# Safety.net
KiCad netlist of a schematic drawn in Altium Designer
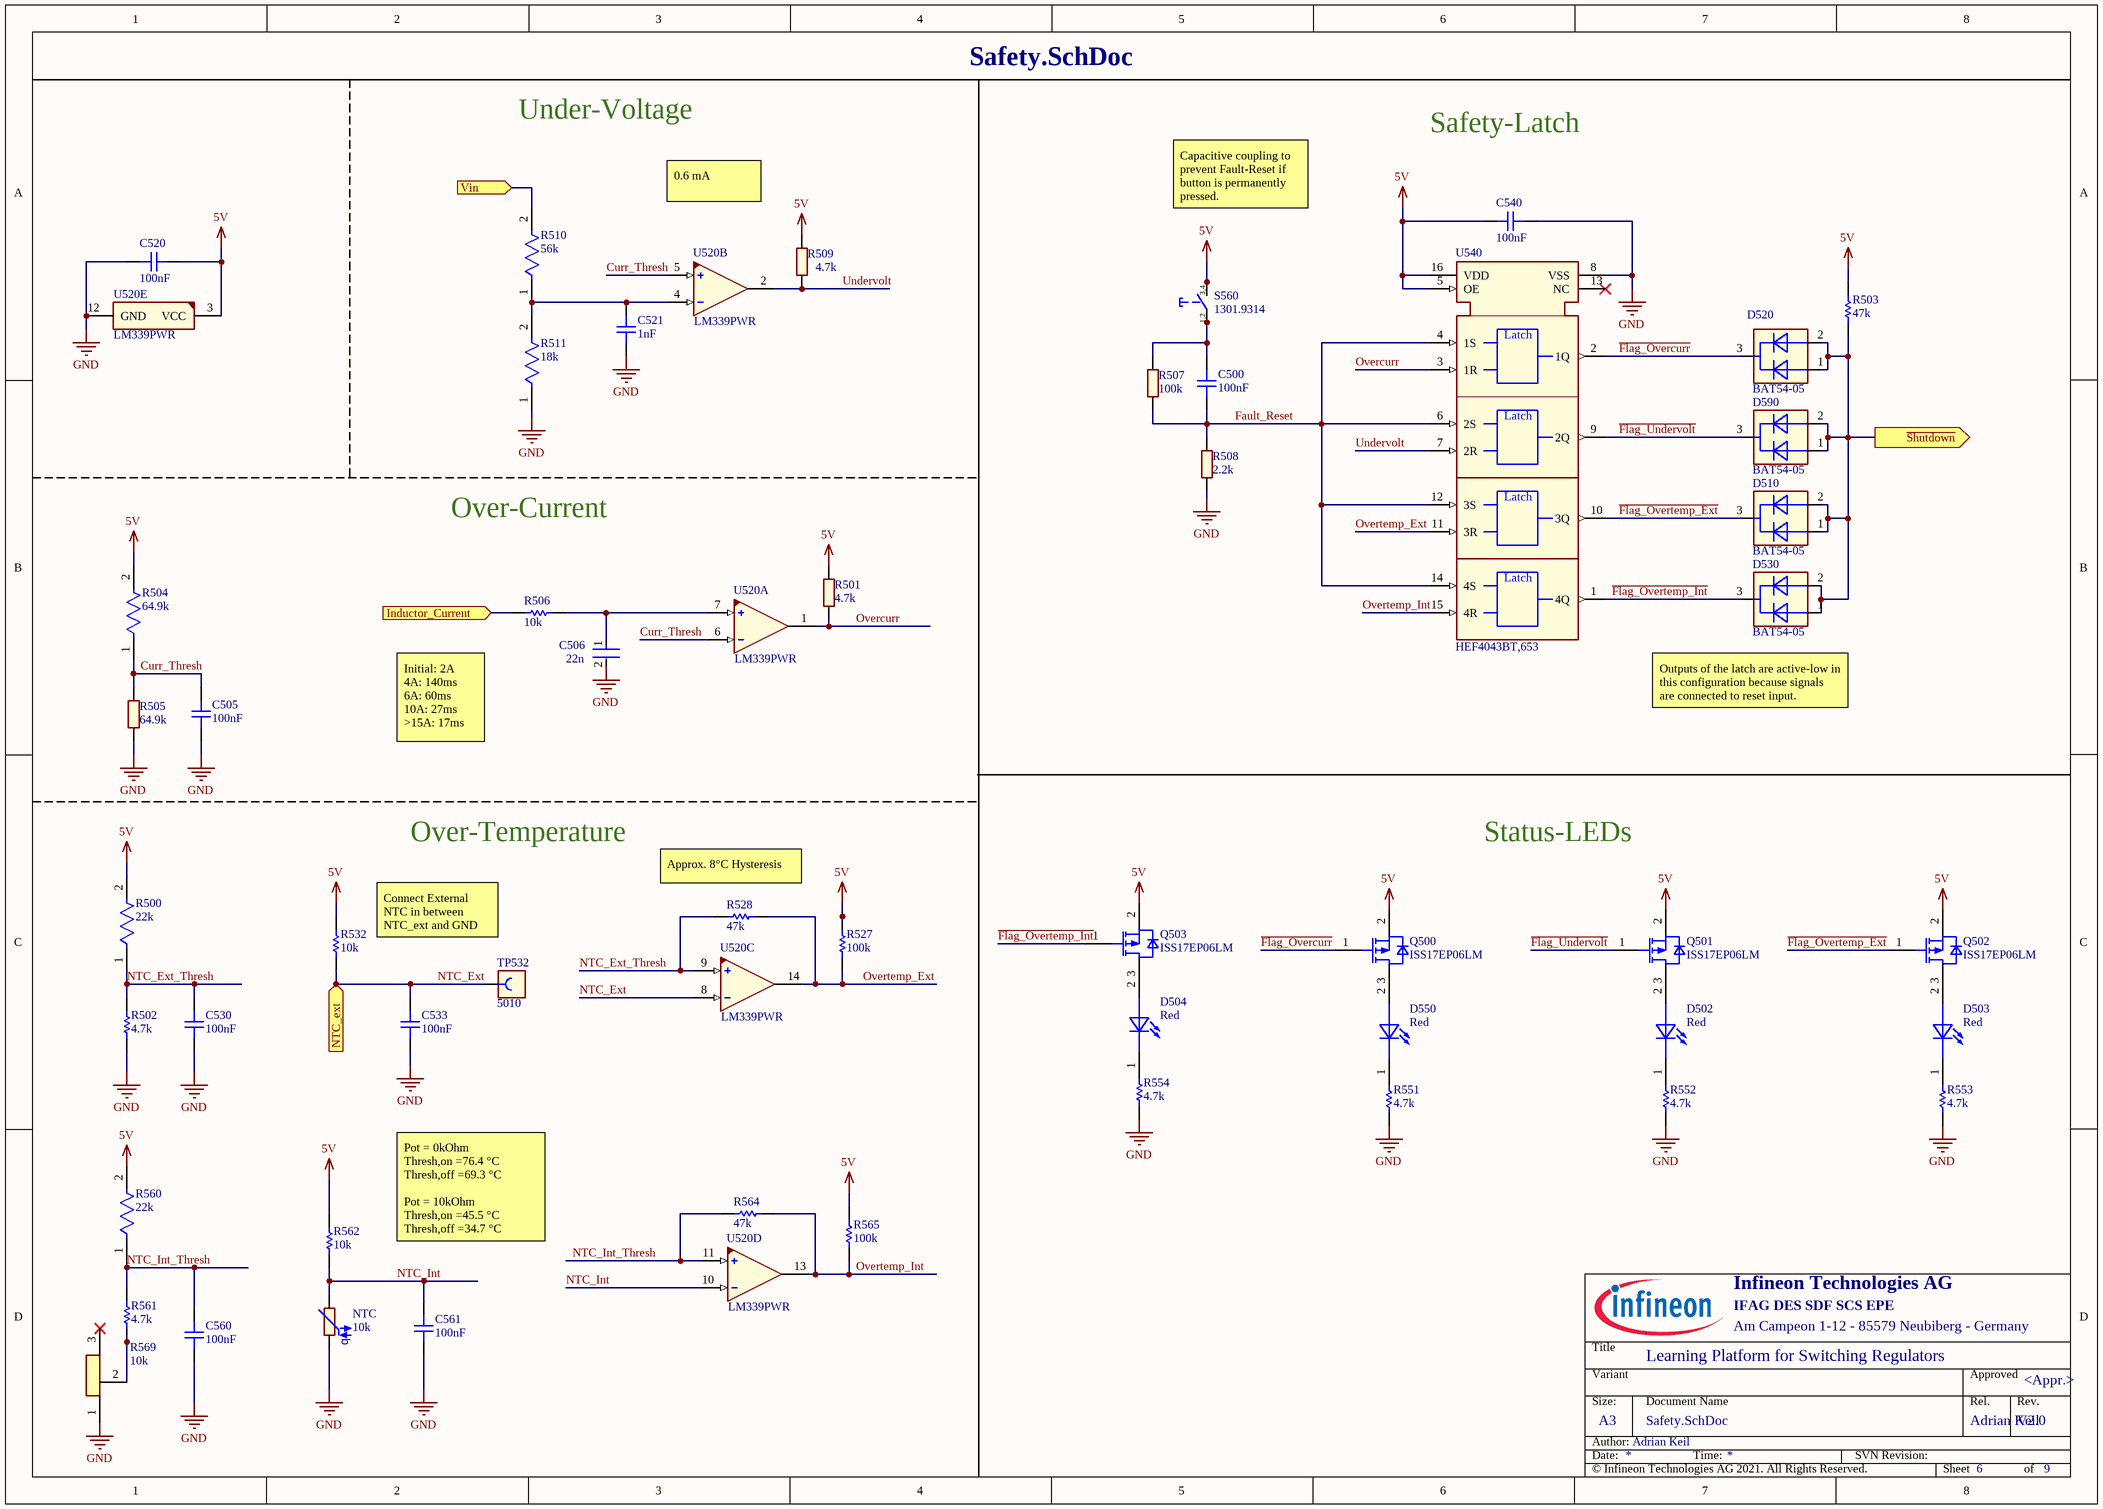
[diagram p0: Safety.SchDoc]

(export (version "E")
  (design (tool "Eeschema 10.0.6"))
  (components
    (comp (ref "C500")
      (value "100nF")
      (footprint "CAPC3216X125N-0")
      (description "CAP / CERA / 100nF / 50V / 10% / X7R (EIA) / -55°C to 125°C / 1206(3216) / SMD / -")
      (fields (field (name "LEGACY PARTNUMBER") "CAP01005660") (field (name "MANUFACTURER") "MuRata"))
      (libsource (lib "PCBLibraryData") (part "CAP-SGL-STD-02P_00000001"))
    )
    (comp (ref "C505")
      (value "100nF")
      (footprint "CAPC3216X125N-0")
      (description "CAP / CERA / 100nF / 50V / 10% / X7R (EIA) / -55°C to 125°C / 1206(3216) / SMD / -")
      (fields (field (name "LEGACY PARTNUMBER") "CAP01005660") (field (name "MANUFACTURER") "MuRata"))
      (libsource (lib "PCBLibraryData") (part "CAP-SGL-STD-02P_00000001"))
    )
    (comp (ref "C506")
      (value "22n")
      (footprint "FP-GRM319-0_15-IPC_C")
      (description "Chip Multilayer Ceramic Capacitors for General Purpose, 1206, 22000pF, C0G, 30ppm/°C, 5%, 50V")
      (fields (field (name "VOLTAGE") "50V") (field (name "TOLERANCE") "5%"))
      (libsource (lib "Altium Content Vault") (part "b4654b650e69147ec39a6b967a45e02"))
    )
    (comp (ref "C520")
      (value "100nF")
      (footprint "CAPC3216X125N-0")
      (description "CAP / CERA / 100nF / 50V / 10% / X7R (EIA) / -55°C to 125°C / 1206(3216) / SMD / -")
      (fields (field (name "LEGACY PARTNUMBER") "CAP01005660") (field (name "MANUFACTURER") "MuRata"))
      (libsource (lib "PCBLibraryData") (part "CAP-SGL-STD-02P_00000001"))
    )
    (comp (ref "C521")
      (value "1nF")
      (footprint "CAPC3216X95N")
      (description "CAP / CERA / 1nF / 50V / 10% / X7R (EIA) / -55°C to 125°C / 1206(3216) / SMD / -")
      (fields (field (name "LEGACY PARTNUMBER") "CAP01005183") (field (name "MANUFACTURER") "MuRata"))
      (libsource (lib "PCBLibraryData") (part "CAP-SGL-STD-02P_00000001"))
    )
    (comp (ref "C530")
      (value "100nF")
      (footprint "CAPC3216X125N-0")
      (description "CAP / CERA / 100nF / 50V / 10% / X7R (EIA) / -55°C to 125°C / 1206(3216) / SMD / -")
      (fields (field (name "LEGACY PARTNUMBER") "CAP01005660") (field (name "MANUFACTURER") "MuRata"))
      (libsource (lib "PCBLibraryData") (part "CAP-SGL-STD-02P_00000001"))
    )
    (comp (ref "C533")
      (value "100nF")
      (footprint "CAPC3216X125N-0")
      (description "CAP / CERA / 100nF / 50V / 10% / X7R (EIA) / -55°C to 125°C / 1206(3216) / SMD / -")
      (fields (field (name "LEGACY PARTNUMBER") "CAP01005660") (field (name "MANUFACTURER") "MuRata"))
      (libsource (lib "PCBLibraryData") (part "CAP-SGL-STD-02P_00000001"))
    )
    (comp (ref "C540")
      (value "100nF")
      (footprint "CAPC3216X125N-0")
      (description "CAP / CERA / 100nF / 50V / 10% / X7R (EIA) / -55°C to 125°C / 1206(3216) / SMD / -")
      (fields (field (name "LEGACY PARTNUMBER") "CAP01005660") (field (name "MANUFACTURER") "MuRata"))
      (libsource (lib "PCBLibraryData") (part "CAP-SGL-STD-02P_00000001"))
    )
    (comp (ref "C560")
      (value "100nF")
      (footprint "CAPC3216X125N-0")
      (description "CAP / CERA / 100nF / 50V / 10% / X7R (EIA) / -55°C to 125°C / 1206(3216) / SMD / -")
      (fields (field (name "LEGACY PARTNUMBER") "CAP01005660") (field (name "MANUFACTURER") "MuRata"))
      (libsource (lib "PCBLibraryData") (part "CAP-SGL-STD-02P_00000001"))
    )
    (comp (ref "C561")
      (value "100nF")
      (footprint "CAPC3216X125N-0")
      (description "CAP / CERA / 100nF / 50V / 10% / X7R (EIA) / -55°C to 125°C / 1206(3216) / SMD / -")
      (fields (field (name "LEGACY PARTNUMBER") "CAP01005660") (field (name "MANUFACTURER") "MuRata"))
      (libsource (lib "PCBLibraryData") (part "CAP-SGL-STD-02P_00000001"))
    )
    (comp (ref "D502")
      (value "Red")
      (footprint "LEDSC160X80X80-2N-1")
      (description "WL-SMCW SMT Mono-color Chip LED Waterclear, Red,630nm")
      (fields (field (name "MANUFACTURER") "Wurth Elektronik"))
      (libsource (lib "PCBLibraryData") (part "d_led_a"))
    )
    (comp (ref "D503")
      (value "Red")
      (footprint "LEDSC160X80X80-2N-1")
      (description "WL-SMCW SMT Mono-color Chip LED Waterclear, Red,630nm")
      (fields (field (name "MANUFACTURER") "Wurth Elektronik"))
      (libsource (lib "PCBLibraryData") (part "d_led_a"))
    )
    (comp (ref "D504")
      (value "Red")
      (footprint "LEDSC160X80X80-2N-1")
      (description "WL-SMCW SMT Mono-color Chip LED Waterclear, Red,630nm")
      (fields (field (name "MANUFACTURER") "Wurth Elektronik"))
      (libsource (lib "PCBLibraryData") (part "d_led_a"))
    )
    (comp (ref "D510")
      (value "BAT54-05")
      (footprint "SOT95P240X110-3N-1-V")
      (description "Silicon Schottky Diode, LS(nH) 1.8, VR 30V")
      (fields
        (field (name "LEGACY PARTNUMBER") "IFX01401370")
        (field (name "MANUFACTURER") "Infineon Technologies")
      )
      (libsource (lib "PCBLibraryData") (part "d_dual_a1a2c3_3p"))
    )
    (comp (ref "D520")
      (value "BAT54-05")
      (footprint "SOT95P240X110-3N-1-V")
      (description "Silicon Schottky Diode, LS(nH) 1.8, VR 30V")
      (fields
        (field (name "LEGACY PARTNUMBER") "IFX01401370")
        (field (name "MANUFACTURER") "Infineon Technologies")
      )
      (libsource (lib "PCBLibraryData") (part "d_dual_a1a2c3_3p"))
    )
    (comp (ref "D530")
      (value "BAT54-05")
      (footprint "SOT95P240X110-3N-1-V")
      (description "Silicon Schottky Diode, LS(nH) 1.8, VR 30V")
      (fields
        (field (name "LEGACY PARTNUMBER") "IFX01401370")
        (field (name "MANUFACTURER") "Infineon Technologies")
      )
      (libsource (lib "PCBLibraryData") (part "d_dual_a1a2c3_3p"))
    )
    (comp (ref "D550")
      (value "Red")
      (footprint "LEDSC160X80X80-2N-1")
      (description "WL-SMCW SMT Mono-color Chip LED Waterclear, Red,630nm")
      (fields (field (name "MANUFACTURER") "Wurth Elektronik"))
      (libsource (lib "PCBLibraryData") (part "d_led_a"))
    )
    (comp (ref "D590")
      (value "BAT54-05")
      (footprint "SOT95P240X110-3N-1-V")
      (description "Silicon Schottky Diode, LS(nH) 1.8, VR 30V")
      (fields
        (field (name "LEGACY PARTNUMBER") "IFX01401370")
        (field (name "MANUFACTURER") "Infineon Technologies")
      )
      (libsource (lib "PCBLibraryData") (part "d_dual_a1a2c3_3p"))
    )
    (comp (ref "NTC")
      (value "10k")
      (footprint "RESC1608X95N-1")
      (description "RES / NTC / 10k / 100mW / 1% / - / -40°C to 125°C / 0603(1608) / SMD / -")
      (fields (field (name "LEGACY PARTNUMBER") "RES01806219") (field (name "MANUFACTURER") "MuRata"))
      (libsource (lib "PCBLibraryData") (part "RES-SGL-NTC-02P_00000007"))
    )
    (comp (ref "Q500")
      (value "ISS17EP06LM")
      (footprint "SOT95P240X110-3N-1-V")
      (description "OptiMOSTM Small Signal Transistor, -60 V")
      (fields (field (name "MANUFACTURER") "Infineon Technologies"))
      (libsource (lib "PCBLibraryData") (part "igfet_p_ch_enh_dio_1g2s3d_3p"))
    )
    (comp (ref "Q501")
      (value "ISS17EP06LM")
      (footprint "SOT95P240X110-3N-1-V")
      (description "OptiMOSTM Small Signal Transistor, -60 V")
      (fields (field (name "MANUFACTURER") "Infineon Technologies"))
      (libsource (lib "PCBLibraryData") (part "igfet_p_ch_enh_dio_1g2s3d_3p"))
    )
    (comp (ref "Q502")
      (value "ISS17EP06LM")
      (footprint "SOT95P240X110-3N-1-V")
      (description "OptiMOSTM Small Signal Transistor, -60 V")
      (fields (field (name "MANUFACTURER") "Infineon Technologies"))
      (libsource (lib "PCBLibraryData") (part "igfet_p_ch_enh_dio_1g2s3d_3p"))
    )
    (comp (ref "Q503")
      (value "ISS17EP06LM")
      (footprint "SOT95P240X110-3N-1-V")
      (description "OptiMOSTM Small Signal Transistor, -60 V")
      (fields (field (name "MANUFACTURER") "Infineon Technologies"))
      (libsource (lib "PCBLibraryData") (part "igfet_p_ch_enh_dio_1g2s3d_3p"))
    )
    (comp (ref "R500")
      (value "22k")
      (footprint "FP-CRCW1206-e3-IPC_A")
      (description "RES Thick Film, 22kΩ, 1%, 0.25W, 100ppm/°C, 1206")
      (fields (field (name "TOLERANCE") "1%"))
      (libsource (lib "Altium Content Vault") (part "1029c3af85768c4190bb7ad29bc67b5"))
    )
    (comp (ref "R501")
      (value "4.7k")
      (footprint "RESC3216X60N")
      (description "RES / STD / 4.7k / 250mW / 1% / 100ppm/K / -55°C to 155°C / 1206(3216) / SMD / -")
      (fields (field (name "LEGACY PARTNUMBER") "RES01802819") (field (name "MANUFACTURER") "Vishay"))
      (libsource (lib "PCBLibraryData") (part "RES-SGL-STD-02P_00000006"))
    )
    (comp (ref "R502")
      (value "4.7k")
      (footprint "RESC3216X60X45ML15T20")
      (description "Chip Resistor, 4.7 KOhm, +/- 1%, 0.25 W, -55 to 155 degC, 1206 (3216 Metric), RoHS, Tape and Reel")
      (fields (field (name "MANUFACTURER") "Vishay Semiconductor") (field (name "TOLERANCE") "1%"))
      (libsource (lib "Altium Content Vault") (part "RES-2"))
    )
    (comp (ref "R503")
      (value "47k")
      (footprint "RESC3216X60X45LL10T20")
      (fields (field (name "PART NUMBER") "CRCW120647K0FKEA") (field (name "MANUFACTURER") "Vishay Dale"))
      (libsource (lib "Altium Content Vault") (part "RES"))
    )
    (comp (ref "R504")
      (value "64.9k")
      (footprint "FP-CRCW1206-e3-IPC_C")
      (description "RES Thick Film, 64.9kΩ, 1%, 0.25W, 100ppm/°C, 1206")
      (fields (field (name "TOLERANCE") "1%") (field (name "LCSC PART #") "C274045"))
      (libsource (lib "Altium Content Vault") (part "1029c3af85768c4190bb7ad29bc67b5"))
    )
    (comp (ref "R505")
      (value "64.9k")
      (footprint "RESC3216X60N")
      (description "RES / STD / 64.9k / 250mW / 1% / 100ppm/K / -55°C to 155°C / 1206(3216) / SMD / -")
      (fields (field (name "LEGACY PARTNUMBER") "RES01802950") (field (name "MANUFACTURER") "Vishay"))
      (libsource (lib "PCBLibraryData") (part "RES-SGL-STD-02P_00000006"))
    )
    (comp (ref "R506")
      (value "10k")
      (footprint "RESC3116X65X50NL20T20")
      (fields
        (field (name "PART NUMBER") "CRCW120610K0FKEAHP")
        (field (name "MANUFACTURER") "Vishay Dale")
        (field (name "LCSC PART #") "C313977")
      )
      (libsource (lib "Altium Content Vault") (part "RES"))
    )
    (comp (ref "R507")
      (value "100k")
      (footprint "RESC3216X60N")
      (description "RES / STD / 100k / 250mW / 1% / 100ppm/K / -55°C to 155°C / 1206(3216) / SMD / -")
      (fields (field (name "LEGACY PARTNUMBER") "RES01802971") (field (name "MANUFACTURER") "Vishay"))
      (libsource (lib "PCBLibraryData") (part "RES-SGL-STD-02P_00000006"))
    )
    (comp (ref "R508")
      (value "2.2k")
      (footprint "RESC3216X60N")
      (description "RES / STD / 2.2k / 250mW / 1% / 100ppm/K / -55°C to 155°C / 1206(3216) / SMD / -")
      (fields (field (name "LEGACY PARTNUMBER") "RES01802779") (field (name "MANUFACTURER") "Vishay"))
      (libsource (lib "") (part "RES-SGL-STD-02P_00000006_1"))
    )
    (comp (ref "R509")
      (value "4.7k")
      (footprint "RESC3216X60N")
      (description "RES / STD / 4.7k / 250mW / 1% / 100ppm/K / -55°C to 155°C / 1206(3216) / SMD / -")
      (fields (field (name "LEGACY PARTNUMBER") "RES01802819") (field (name "MANUFACTURER") "Vishay"))
      (libsource (lib "PCBLibraryData") (part "RES-SGL-STD-02P_00000006"))
    )
    (comp (ref "R510")
      (value "56k")
      (footprint "FP-CRCW1206-e3-IPC_C")
      (description "RES Thick Film, 56kΩ, 1%, 0.25W, 100ppm/°C, 1206")
      (fields (field (name "TOLERANCE") "1%") (field (name "LCSC PART #") "C137251"))
      (libsource (lib "Altium Content Vault") (part "1029c3af85768c4190bb7ad29bc67b5"))
    )
    (comp (ref "R511")
      (value "18k")
      (footprint "FP-CRCW1206-e3-IPC_C")
      (description "RES Thick Film, 18kΩ, 1%, 0.25W, 100ppm/°C, 1206")
      (fields (field (name "TOLERANCE") "1%"))
      (libsource (lib "Altium Content Vault") (part "1029c3af85768c4190bb7ad29bc67b5"))
    )
    (comp (ref "R527")
      (value "100k")
      (footprint "RESC3216X60X45NL10T20")
      (fields (field (name "PART NUMBER") "CRCW1206100KFKEA") (field (name "MANUFACTURER") "Vishay Dale"))
      (libsource (lib "Altium Content Vault") (part "RES"))
    )
    (comp (ref "R528")
      (value "47k")
      (footprint "RESC3216X60X45LL10T20")
      (fields (field (name "PART NUMBER") "CRCW120647K0FKEA") (field (name "MANUFACTURER") "Vishay Dale"))
      (libsource (lib "Altium Content Vault") (part "RES"))
    )
    (comp (ref "R532")
      (value "10k")
      (footprint "RESC3116X65X50NL20T20")
      (fields (field (name "PART NUMBER") "CRCW120610K0FKEAHP") (field (name "MANUFACTURER") "Vishay Dale"))
      (libsource (lib "Altium Content Vault") (part "RES"))
    )
    (comp (ref "R551")
      (value "4.7k")
      (footprint "RESC3216X60X45ML15T20")
      (description "Chip Resistor, 4.7 KOhm, +/- 1%, 0.25 W, -55 to 155 degC, 1206 (3216 Metric), RoHS, Tape and Reel")
      (fields (field (name "MANUFACTURER") "Vishay Semiconductor") (field (name "TOLERANCE") "1%"))
      (libsource (lib "Altium Content Vault") (part "RES-2"))
    )
    (comp (ref "R552")
      (value "4.7k")
      (footprint "RESC3216X60X45ML15T20")
      (description "Chip Resistor, 4.7 KOhm, +/- 1%, 0.25 W, -55 to 155 degC, 1206 (3216 Metric), RoHS, Tape and Reel")
      (fields (field (name "MANUFACTURER") "Vishay Semiconductor") (field (name "TOLERANCE") "1%"))
      (libsource (lib "Altium Content Vault") (part "RES-2"))
    )
    (comp (ref "R553")
      (value "4.7k")
      (footprint "RESC3216X60X45ML15T20")
      (description "Chip Resistor, 4.7 KOhm, +/- 1%, 0.25 W, -55 to 155 degC, 1206 (3216 Metric), RoHS, Tape and Reel")
      (fields (field (name "MANUFACTURER") "Vishay Semiconductor") (field (name "TOLERANCE") "1%"))
      (libsource (lib "Altium Content Vault") (part "RES-2"))
    )
    (comp (ref "R554")
      (value "4.7k")
      (footprint "RESC3216X60X45ML15T20")
      (description "Chip Resistor, 4.7 KOhm, +/- 1%, 0.25 W, -55 to 155 degC, 1206 (3216 Metric), RoHS, Tape and Reel")
      (fields (field (name "MANUFACTURER") "Vishay Semiconductor") (field (name "TOLERANCE") "1%"))
      (libsource (lib "Altium Content Vault") (part "RES-2"))
    )
    (comp (ref "R560")
      (value "22k")
      (footprint "FP-CRCW1206-e3-IPC_A")
      (description "RES Thick Film, 22kΩ, 1%, 0.25W, 100ppm/°C, 1206")
      (fields (field (name "TOLERANCE") "1%"))
      (libsource (lib "Altium Content Vault") (part "1029c3af85768c4190bb7ad29bc67b5"))
    )
    (comp (ref "R561")
      (value "4.7k")
      (footprint "RESC3216X60X45ML15T20")
      (description "Chip Resistor, 4.7 KOhm, +/- 1%, 0.25 W, -55 to 155 degC, 1206 (3216 Metric), RoHS, Tape and Reel")
      (fields (field (name "MANUFACTURER") "Vishay Semiconductor") (field (name "TOLERANCE") "1%"))
      (libsource (lib "Altium Content Vault") (part "RES-2"))
    )
    (comp (ref "R562")
      (value "10k")
      (footprint "RESC3116X65X50NL20T20")
      (fields (field (name "PART NUMBER") "CRCW120610K0FKEAHP") (field (name "MANUFACTURER") "Vishay Dale"))
      (libsource (lib "Altium Content Vault") (part "RES"))
    )
    (comp (ref "R564")
      (value "47k")
      (footprint "RESC3216X60X45LL10T20")
      (fields (field (name "PART NUMBER") "CRCW120647K0FKEA") (field (name "MANUFACTURER") "Vishay Dale"))
      (libsource (lib "Altium Content Vault") (part "RES"))
    )
    (comp (ref "R565")
      (value "100k")
      (footprint "RESC3216X60X45NL10T20")
      (fields (field (name "PART NUMBER") "CRCW1206100KFKEA") (field (name "MANUFACTURER") "Vishay Dale"))
      (libsource (lib "Altium Content Vault") (part "RES"))
    )
    (comp (ref "R569")
      (value "10k")
      (footprint "myPcbLib:3361P1103GLF")
      (description "Variable Resistor")
      (fields
        (field (name "MANUFACTURER_PART_NUMBER") "3361P-1-103GLF")
        (field (name "MOUSER PART NUMBER") "652-3361P-1-103GLF")
      )
      (libsource (lib "mySchlib") (part "3361P-1-103GLF"))
    )
    (comp (ref "S560")
      (value "1301.9314")
      (footprint "SW-SMD-1301.9314")
      (description "Pushbutton Tactile Switch, Single Pole Single Throw, 4 Pins")
      (fields (field (name "LEGACY PARTNUMBER") "CON01500305") (field (name "MANUFACTURER") "Schurter"))
      (libsource (lib "PCBLibraryData") (part "sw_sr_no12_34_4p"))
    )
    (comp (ref "TP532")
      (value "5010")
      (footprint "CON-THT-TP-5010")
      (description "PC Test Point-Multipurpose THT, Red")
      (fields
        (field (name "LEGACY PARTNUMBER") "CON01500529")
        (field (name "MANUFACTURER") "Keystone Electronics Corp.")
      )
      (libsource (lib "PCBLibraryData") (part "connector_1_f"))
    )
    (comp (ref "U520")
      (value "LM339PWR")
      (footprint "SOP65P640X120-14N-1")
      (description "Quad Differential Comparator")
      (fields
        (field (name "LEGACY PARTNUMBER") "IC02600564")
        (field (name "MANUFACTURER") "Texas Instruments")
      )
      (libsource (lib "PCBLibraryData") (part "LM339PWR"))
    )
    (comp (ref "U540")
      (value "HEF4043BT,653")
      (footprint "SOIC127P600X175-16N-6")
      (description "Quad R/S latch with 3-state outputs")
      (fields (field (name "MANUFACTURER") "Nexperia"))
      (libsource (lib "PCBLibraryData") (part "HEF4043B"))
    )
  )
  (nets
    (net (code "1") (name "/Curr_Thresh") (class "Default")
      (node (ref "C505") (pin "2") (pinfunction "2_2") (pintype "passive"))
      (node (ref "R504") (pin "1") (pinfunction "1_1") (pintype "passive"))
      (node (ref "R505") (pin "2") (pinfunction "2_2") (pintype "passive"))
      (node (ref "U520") (pin "5") (pinfunction "2IN_P_5") (pintype "input"))
      (node (ref "U520") (pin "6") (pinfunction "1IN_N_6") (pintype "input"))
    )
    (net (code "2") (name "/Fault_Reset") (class "Default")
      (node (ref "C500") (pin "2") (pinfunction "2_2") (pintype "passive"))
      (node (ref "R507") (pin "1") (pinfunction "1_1") (pintype "passive"))
      (node (ref "R508") (pin "1") (pinfunction "1_1") (pintype "passive"))
      (node (ref "U540") (pin "12") (pinfunction "3S_12") (pintype "input"))
      (node (ref "U540") (pin "14") (pinfunction "4S_14") (pintype "input"))
      (node (ref "U540") (pin "4") (pinfunction "1S_4") (pintype "input"))
      (node (ref "U540") (pin "6") (pinfunction "2S_6") (pintype "input"))
    )
    (net (code "3") (name "/Flag_Overcurr") (class "Default")
      (node (ref "D520") (pin "3") (pinfunction "CATHODE_3") (pintype "passive"))
      (node (ref "Q500") (pin "1") (pinfunction "GATE_1") (pintype "passive"))
      (node (ref "U540") (pin "2") (pinfunction "1Q_2") (pintype "output"))
    )
    (net (code "4") (name "/Flag_Overtemp_Ext") (class "Default")
      (node (ref "D510") (pin "3") (pinfunction "CATHODE_3") (pintype "passive"))
      (node (ref "Q502") (pin "1") (pinfunction "GATE_1") (pintype "passive"))
      (node (ref "U540") (pin "10") (pinfunction "3Q_10") (pintype "output"))
    )
    (net (code "5") (name "/Flag_Overtemp_Int") (class "Default")
      (node (ref "D530") (pin "3") (pinfunction "CATHODE_3") (pintype "passive"))
      (node (ref "Q503") (pin "1") (pinfunction "GATE_1") (pintype "passive"))
      (node (ref "U540") (pin "1") (pinfunction "4Q_1") (pintype "output"))
    )
    (net (code "6") (name "/Flag_Undervolt") (class "Default")
      (node (ref "D590") (pin "3") (pinfunction "CATHODE_3") (pintype "passive"))
      (node (ref "Q501") (pin "1") (pinfunction "GATE_1") (pintype "passive"))
      (node (ref "U540") (pin "9") (pinfunction "2Q_9") (pintype "output"))
    )
    (net (code "7") (name "/Inductor_Current") (class "Default")
      (node (ref "R506") (pin "1") (pinfunction "1_1") (pintype "passive"))
    )
    (net (code "8") (name "/NTC_Ext") (class "Default")
      (node (ref "C533") (pin "2") (pinfunction "2_2") (pintype "passive"))
      (node (ref "R532") (pin "1") (pinfunction "1_1") (pintype "passive"))
      (node (ref "TP532") (pin "1") (pinfunction "1_1") (pintype "passive"))
      (node (ref "U520") (pin "8") (pinfunction "3IN_N_8") (pintype "input"))
    )
    (net (code "9") (name "/NTC_Ext_Thresh") (class "Default")
      (node (ref "C530") (pin "2") (pinfunction "2_2") (pintype "passive"))
      (node (ref "R500") (pin "1") (pinfunction "1_1") (pintype "passive"))
      (node (ref "R502") (pin "2") (pinfunction "2_2") (pintype "passive"))
      (node (ref "R528") (pin "1") (pinfunction "1_1") (pintype "passive"))
      (node (ref "U520") (pin "9") (pinfunction "3IN_P_9") (pintype "input"))
    )
    (net (code "10") (name "/NTC_Int") (class "Default")
      (node (ref "C561") (pin "2") (pinfunction "2_2") (pintype "passive"))
      (node (ref "NTC") (pin "2") (pinfunction "2_2") (pintype "passive"))
      (node (ref "R562") (pin "1") (pinfunction "1_1") (pintype "passive"))
      (node (ref "U520") (pin "10") (pinfunction "4IN_N_10") (pintype "input"))
    )
    (net (code "11") (name "/NTC_Int_Thresh") (class "Default")
      (node (ref "C560") (pin "2") (pinfunction "2_2") (pintype "passive"))
      (node (ref "R560") (pin "1") (pinfunction "1_1") (pintype "passive"))
      (node (ref "R561") (pin "2") (pinfunction "2_2") (pintype "passive"))
      (node (ref "R564") (pin "1") (pinfunction "1_1") (pintype "passive"))
      (node (ref "U520") (pin "11") (pinfunction "4IN_P_11") (pintype "input"))
    )
    (net (code "12") (name "/Overcurr") (class "Default")
      (node (ref "R501") (pin "1") (pinfunction "1_1") (pintype "passive"))
      (node (ref "U520") (pin "1") (pinfunction "1OUT_1") (pintype "open_collector"))
      (node (ref "U540") (pin "3") (pinfunction "1R_3") (pintype "input"))
    )
    (net (code "13") (name "/Overtemp_Ext") (class "Default")
      (node (ref "R527") (pin "1") (pinfunction "1_1") (pintype "passive"))
      (node (ref "R528") (pin "2") (pinfunction "2_2") (pintype "passive"))
      (node (ref "U520") (pin "14") (pinfunction "3OUT_14") (pintype "open_collector"))
      (node (ref "U540") (pin "11") (pinfunction "3R_11") (pintype "input"))
    )
    (net (code "14") (name "/Overtemp_Int") (class "Default")
      (node (ref "R564") (pin "2") (pinfunction "2_2") (pintype "passive"))
      (node (ref "R565") (pin "1") (pinfunction "1_1") (pintype "passive"))
      (node (ref "U520") (pin "13") (pinfunction "4OUT_13") (pintype "open_collector"))
      (node (ref "U540") (pin "15") (pinfunction "4R_15") (pintype "input"))
    )
    (net (code "15") (name "/Shutdown") (class "Default")
      (node (ref "D510") (pin "1") (pinfunction "ANODE_1_1") (pintype "passive"))
      (node (ref "D510") (pin "2") (pinfunction "ANODE_2_2") (pintype "passive"))
      (node (ref "D520") (pin "1") (pinfunction "ANODE_1_1") (pintype "passive"))
      (node (ref "D520") (pin "2") (pinfunction "ANODE_2_2") (pintype "passive"))
      (node (ref "D530") (pin "1") (pinfunction "ANODE_1_1") (pintype "passive"))
      (node (ref "D530") (pin "2") (pinfunction "ANODE_2_2") (pintype "passive"))
      (node (ref "D590") (pin "1") (pinfunction "ANODE_1_1") (pintype "passive"))
      (node (ref "D590") (pin "2") (pinfunction "ANODE_2_2") (pintype "passive"))
      (node (ref "R503") (pin "1") (pinfunction "1_1") (pintype "passive"))
    )
    (net (code "16") (name "/Undervolt") (class "Default")
      (node (ref "R509") (pin "1") (pinfunction "1_1") (pintype "passive"))
      (node (ref "U520") (pin "2") (pinfunction "2OUT_2") (pintype "open_collector"))
      (node (ref "U540") (pin "7") (pinfunction "2R_7") (pintype "input"))
    )
    (net (code "17") (name "/Vin") (class "Default")
      (node (ref "R510") (pin "2") (pinfunction "2_2") (pintype "passive"))
    )
    (net (code "18") (name "5V") (class "Default")
      (node (ref "C520") (pin "1") (pinfunction "1_1") (pintype "passive"))
      (node (ref "C540") (pin "2") (pinfunction "2_2") (pintype "passive"))
      (node (ref "Q500") (pin "2") (pinfunction "SOURCE_2") (pintype "passive"))
      (node (ref "Q501") (pin "2") (pinfunction "SOURCE_2") (pintype "passive"))
      (node (ref "Q502") (pin "2") (pinfunction "SOURCE_2") (pintype "passive"))
      (node (ref "Q503") (pin "2") (pinfunction "SOURCE_2") (pintype "passive"))
      (node (ref "R500") (pin "2") (pinfunction "2_2") (pintype "passive"))
      (node (ref "R501") (pin "2") (pinfunction "2_2") (pintype "passive"))
      (node (ref "R503") (pin "2") (pinfunction "2_2") (pintype "passive"))
      (node (ref "R504") (pin "2") (pinfunction "2_2") (pintype "passive"))
      (node (ref "R509") (pin "2") (pinfunction "2_2") (pintype "passive"))
      (node (ref "R527") (pin "2") (pinfunction "2_2") (pintype "passive"))
      (node (ref "R532") (pin "2") (pinfunction "2_2") (pintype "passive"))
      (node (ref "R560") (pin "2") (pinfunction "2_2") (pintype "passive"))
      (node (ref "R562") (pin "2") (pinfunction "2_2") (pintype "passive"))
      (node (ref "R565") (pin "2") (pinfunction "2_2") (pintype "passive"))
      (node (ref "S560") (pin "3") (pinfunction "3_3") (pintype "passive"))
      (node (ref "S560") (pin "4") (pinfunction "4_4") (pintype "passive"))
      (node (ref "U520") (pin "3") (pinfunction "VCC_3") (pintype "power_in"))
      (node (ref "U540") (pin "16") (pinfunction "VDD_16") (pintype "power_in"))
      (node (ref "U540") (pin "5") (pinfunction "OE_5") (pintype "input"))
    )
    (net (code "19") (name "GND") (class "Default")
      (node (ref "C505") (pin "1") (pinfunction "1_1") (pintype "passive"))
      (node (ref "C506") (pin "2") (pinfunction "2_2") (pintype "passive"))
      (node (ref "C520") (pin "2") (pinfunction "2_2") (pintype "passive"))
      (node (ref "C521") (pin "1") (pinfunction "1_1") (pintype "passive"))
      (node (ref "C530") (pin "1") (pinfunction "1_1") (pintype "passive"))
      (node (ref "C533") (pin "1") (pinfunction "1_1") (pintype "passive"))
      (node (ref "C540") (pin "1") (pinfunction "1_1") (pintype "passive"))
      (node (ref "C560") (pin "1") (pinfunction "1_1") (pintype "passive"))
      (node (ref "C561") (pin "1") (pinfunction "1_1") (pintype "passive"))
      (node (ref "NTC") (pin "1") (pinfunction "1_1") (pintype "passive"))
      (node (ref "R502") (pin "1") (pinfunction "1_1") (pintype "passive"))
      (node (ref "R505") (pin "1") (pinfunction "1_1") (pintype "passive"))
      (node (ref "R508") (pin "2") (pinfunction "2_2") (pintype "passive"))
      (node (ref "R511") (pin "1") (pinfunction "1_1") (pintype "passive"))
      (node (ref "R551") (pin "1") (pinfunction "1_1") (pintype "passive"))
      (node (ref "R552") (pin "1") (pinfunction "1_1") (pintype "passive"))
      (node (ref "R553") (pin "1") (pinfunction "1_1") (pintype "passive"))
      (node (ref "R554") (pin "1") (pinfunction "1_1") (pintype "passive"))
      (node (ref "R569") (pin "1") (pinfunction "CCW_1") (pintype "passive"))
      (node (ref "U520") (pin "12") (pinfunction "GND_12") (pintype "power_in"))
      (node (ref "U540") (pin "8") (pinfunction "VSS_8") (pintype "power_in"))
    )
    (net (code "20") (name "Net-(C500-Pad1)") (class "Default")
      (node (ref "C500") (pin "1") (pinfunction "1_1") (pintype "passive"))
      (node (ref "R507") (pin "2") (pinfunction "2_2") (pintype "passive"))
      (node (ref "S560") (pin "1") (pinfunction "1_1") (pintype "passive"))
      (node (ref "S560") (pin "2") (pinfunction "2_2") (pintype "passive"))
    )
    (net (code "21") (name "Net-(D502-Anode)") (class "Default")
      (node (ref "D502") (pin "2") (pinfunction "Anode_2") (pintype "passive"))
      (node (ref "Q501") (pin "3") (pinfunction "DRAIN_3") (pintype "passive"))
    )
    (net (code "22") (name "Net-(D502-Cathode)") (class "Default")
      (node (ref "D502") (pin "1") (pinfunction "Cathode_1") (pintype "passive"))
      (node (ref "R552") (pin "2") (pinfunction "2_2") (pintype "passive"))
    )
    (net (code "23") (name "Net-(D503-Anode)") (class "Default")
      (node (ref "D503") (pin "2") (pinfunction "Anode_2") (pintype "passive"))
      (node (ref "Q502") (pin "3") (pinfunction "DRAIN_3") (pintype "passive"))
    )
    (net (code "24") (name "Net-(D503-Cathode)") (class "Default")
      (node (ref "D503") (pin "1") (pinfunction "Cathode_1") (pintype "passive"))
      (node (ref "R553") (pin "2") (pinfunction "2_2") (pintype "passive"))
    )
    (net (code "25") (name "Net-(D504-Anode)") (class "Default")
      (node (ref "D504") (pin "2") (pinfunction "Anode_2") (pintype "passive"))
      (node (ref "Q503") (pin "3") (pinfunction "DRAIN_3") (pintype "passive"))
    )
    (net (code "26") (name "Net-(D504-Cathode)") (class "Default")
      (node (ref "D504") (pin "1") (pinfunction "Cathode_1") (pintype "passive"))
      (node (ref "R554") (pin "2") (pinfunction "2_2") (pintype "passive"))
    )
    (net (code "27") (name "Net-(D550-Anode)") (class "Default")
      (node (ref "D550") (pin "2") (pinfunction "Anode_2") (pintype "passive"))
      (node (ref "Q500") (pin "3") (pinfunction "DRAIN_3") (pintype "passive"))
    )
    (net (code "28") (name "Net-(D550-Cathode)") (class "Default")
      (node (ref "D550") (pin "1") (pinfunction "Cathode_1") (pintype "passive"))
      (node (ref "R551") (pin "2") (pinfunction "2_2") (pintype "passive"))
    )
    (net (code "29") (name "Net-(R569-WIPER_)") (class "Default")
      (node (ref "R561") (pin "1") (pinfunction "1_1") (pintype "passive"))
      (node (ref "R569") (pin "2") (pinfunction "WIPER__2") (pintype "passive"))
    )
    (net (code "30") (name "Net-(U520A-1IN_P)") (class "Default")
      (node (ref "C506") (pin "1") (pinfunction "1_1") (pintype "passive"))
      (node (ref "R506") (pin "2") (pinfunction "2_2") (pintype "passive"))
      (node (ref "U520") (pin "7") (pinfunction "1IN_P_7") (pintype "input"))
    )
    (net (code "31") (name "Net-(U520B-2IN_N)") (class "Default")
      (node (ref "C521") (pin "2") (pinfunction "2_2") (pintype "passive"))
      (node (ref "R510") (pin "1") (pinfunction "1_1") (pintype "passive"))
      (node (ref "R511") (pin "2") (pinfunction "2_2") (pintype "passive"))
      (node (ref "U520") (pin "4") (pinfunction "2IN_N_4") (pintype "input"))
    )
    (net (code "32") (name "unconnected-(R569-CW-Pad3)") (class "Default")
      (node (ref "R569") (pin "3") (pinfunction "CW_3") (pintype "passive+no_connect"))
    )
    (net (code "33") (name "unconnected-(U540-NC-Pad13)") (class "Default")
      (node (ref "U540") (pin "13") (pinfunction "NC_13") (pintype "passive+no_connect"))
    )
  )
)
